# STB_PSU.net
KiCad netlist of a schematic drawn in Altium Designer
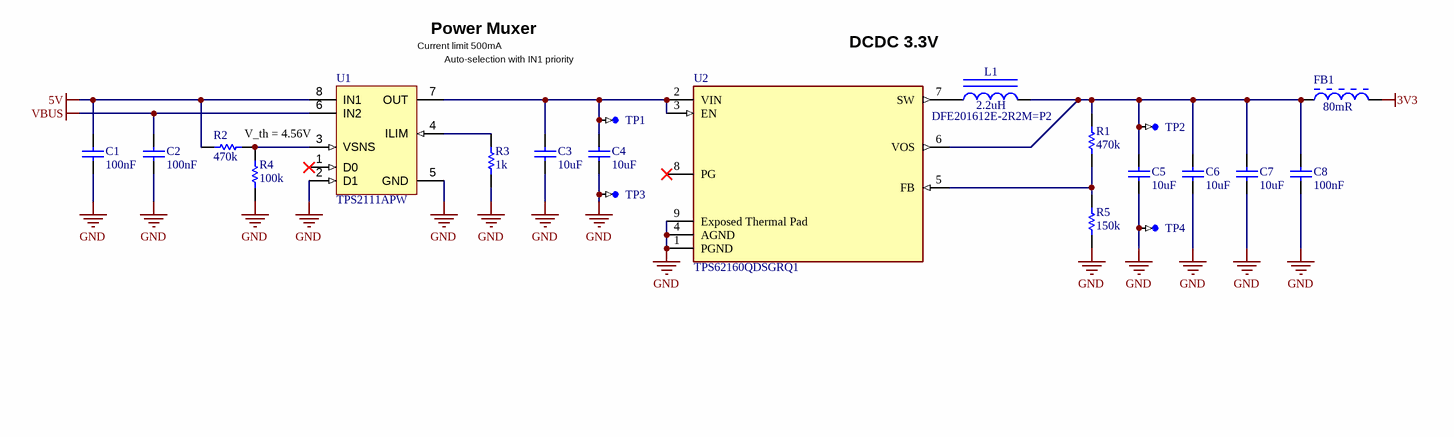
[diagram p0: STB_PSU.SchDoc]

(export (version "E")
  (design (tool "Eeschema 10.0.6"))
  (components
    (comp (ref "C1")
      (value "100nF")
      (footprint "CAPC1050X55X23LL05T13")
      (description "Chip Capacitor, 100 nF, +/- 10%, 16 V, -55 to 125 degC, 0402 (1005 Metric), RoHS, Tape and Reel")
      (fields
        (field (name "MANUFACTURER") "Samsung Electro-Mechanics")
        (field (name "MANUFACTURER PART NUMBER") "CL05B104KO5NNNC")
      )
      (libsource (lib "Altium Content Vault") (part "CAP-NP-2"))
    )
    (comp (ref "C2")
      (value "100nF")
      (footprint "CAPC1050X55X23LL05T13")
      (description "Chip Capacitor, 100 nF, +/- 10%, 16 V, -55 to 125 degC, 0402 (1005 Metric), RoHS, Tape and Reel")
      (fields
        (field (name "MANUFACTURER") "Samsung Electro-Mechanics")
        (field (name "MANUFACTURER PART NUMBER") "CL05B104KO5NNNC")
      )
      (libsource (lib "Altium Content Vault") (part "CAP-NP-2"))
    )
    (comp (ref "C3")
      (value "10uF")
      (footprint "CAPC0603(1608)100_L")
      (description "CAP 10uF 10V ±10% 0603 (1608 Metric) Thickness 1mm SMD")
      (fields (field (name "TOLERANCE") "Â±10%") (field (name "MANUFACTURER") "Samsung"))
      (libsource (lib "Altium Content Vault") (part "CMP-1035-02799-1"))
    )
    (comp (ref "C4")
      (value "10uF")
      (footprint "CAPC0603(1608)100_L")
      (description "CAP 10uF 10V ±10% 0603 (1608 Metric) Thickness 1mm SMD")
      (fields (field (name "TOLERANCE") "Â±10%") (field (name "MANUFACTURER") "Samsung"))
      (libsource (lib "Altium Content Vault") (part "CMP-1035-02799-1"))
    )
    (comp (ref "C5")
      (value "10uF")
      (footprint "CAPC0603(1608)100_L")
      (description "CAP 10uF 10V ±10% 0603 (1608 Metric) Thickness 1mm SMD")
      (fields (field (name "TOLERANCE") "Â±10%") (field (name "MANUFACTURER") "Samsung"))
      (libsource (lib "Altium Content Vault") (part "CMP-1035-02799-1"))
    )
    (comp (ref "C6")
      (value "10uF")
      (footprint "CAPC0603(1608)100_L")
      (description "CAP 10uF 10V ±10% 0603 (1608 Metric) Thickness 1mm SMD")
      (fields (field (name "TOLERANCE") "Â±10%") (field (name "MANUFACTURER") "Samsung"))
      (libsource (lib "Altium Content Vault") (part "CMP-1035-02799-1"))
    )
    (comp (ref "C7")
      (value "10uF")
      (footprint "CAPC0603(1608)100_L")
      (description "CAP 10uF 10V ±10% 0603 (1608 Metric) Thickness 1mm SMD")
      (fields (field (name "TOLERANCE") "Â±10%") (field (name "MANUFACTURER") "Samsung"))
      (libsource (lib "Altium Content Vault") (part "CMP-1035-02799-1"))
    )
    (comp (ref "C8")
      (value "100nF")
      (footprint "CAPC1050X55X23LL05T13")
      (description "Chip Capacitor, 100 nF, +/- 10%, 16 V, -55 to 125 degC, 0402 (1005 Metric), RoHS, Tape and Reel")
      (fields
        (field (name "MANUFACTURER") "Samsung Electro-Mechanics")
        (field (name "MANUFACTURER PART NUMBER") "CL05B104KO5NNNC")
      )
      (libsource (lib "Altium Content Vault") (part "CAP-NP-2"))
    )
    (comp (ref "FB1")
      (value "80mR")
      (footprint "MURA-BLM03-CHIP-2_V")
      (fields
        (field (name "MANUFACTURER") "Murata")
        (field (name "PARTNUMBER") "BLM03AX800SN1D")
        (field (name "TOLERANCE") "25%")
      )
      (libsource (lib "Altium Content Vault") (part "MURA-FB-2"))
    )
    (comp (ref "L1")
      (value "DFE201612E-2R2M=P2")
      (footprint "INDC2016X10L")
      (description "2.2µH Shielded Wirewound Inductor 1.8A 116mOhm Max 0806 (2016 Metric)")
      (fields
        (field (name "ALTIUM_VALUE") "2.2uH")
        (field (name "TOLERANCE") "±20%")
        (field (name "MANUFACTURER") "Murata Electronics")
      )
      (libsource (lib "ETHZ Vault") (part "Iron Core Inductor"))
    )
    (comp (ref "R1")
      (value "470k")
      (footprint "RESC1005X40X25LL05T10")
      (fields
        (field (name "PART NUMBER") "RC0402FR-07470KL")
        (field (name "MANUFACTURER") "Yageo / Phycomp")
        (field (name "TOLERANCE") "1%")
      )
      (libsource (lib "Altium Content Vault") (part "RES"))
    )
    (comp (ref "R2")
      (value "470k")
      (footprint "RESC1005X40X25LL05T10")
      (fields
        (field (name "PART NUMBER") "RC0402FR-07470KL")
        (field (name "MANUFACTURER") "Yageo / Phycomp")
        (field (name "TOLERANCE") "1%")
      )
      (libsource (lib "Altium Content Vault") (part "RES"))
    )
    (comp (ref "R3")
      (value "1k")
      (footprint "RESC1005X40X25LL05T10")
      (fields
        (field (name "PART NUMBER") "RC0402FR-071KL")
        (field (name "MANUFACTURER") "Yageo / Phycomp")
        (field (name "TOLERANCE") "1%")
      )
      (libsource (lib "Altium Content Vault") (part "RES"))
    )
    (comp (ref "R4")
      (value "100k")
      (footprint "RESC1005X40X25LL05T10")
      (fields
        (field (name "PART NUMBER") "RC0402FR-07100KL")
        (field (name "MANUFACTURER") "Yageo / Phycomp")
        (field (name "TOLERANCE") "1%")
      )
      (libsource (lib "Altium Content Vault") (part "RES"))
    )
    (comp (ref "R5")
      (value "150k")
      (footprint "RESC1005X40X25LL05T05")
      (fields
        (field (name "MANUFACTURER") "Yageo")
        (field (name "MANUFACTURER PART NUMBER") "RC0402FR-07150KL")
        (field (name "TOLERANCE") "1%")
      )
      (libsource (lib "Altium Content Vault") (part "RES"))
    )
    (comp (ref "TP1")
      (value "TP_1mm")
      (footprint "TP-SM-C-100")
      (description "testPoint 1mm")
      (libsource (lib "STB_Schlib") (part "testPoint_1mm"))
    )
    (comp (ref "TP2")
      (value "TP_1mm")
      (footprint "TP-SM-C-100")
      (description "testPoint 1mm")
      (libsource (lib "STB_Schlib") (part "testPoint_1mm"))
    )
    (comp (ref "TP3")
      (value "TP_1mm")
      (footprint "TP-SM-C-100")
      (description "testPoint 1mm")
      (libsource (lib "STB_Schlib") (part "testPoint_1mm"))
    )
    (comp (ref "TP4")
      (value "TP_1mm")
      (footprint "TP-SM-C-100")
      (description "testPoint 1mm")
      (libsource (lib "STB_Schlib") (part "testPoint_1mm"))
    )
    (comp (ref "U1")
      (value "TPS2111APW")
      (footprint "PW0008A_N")
      (fields (field (name "MANUFACTURER") "Texas Instruments"))
      (libsource (lib "Altium Content Vault") (part "TI-TPS2111APW8"))
    )
    (comp (ref "U2")
      (value "TPS62160QDSGRQ1")
      (footprint "FP-DSG0008A-IPC_C")
      (description "IC REG BUCK ADJUSTABLE 1A 8WSON")
      (fields (field (name "MANUFACTURER") "Texas Instruments"))
      (libsource (lib "Altium Content Vault") (part "e17a5803605875dd2ffdf80d518602c"))
    )
  )
  (nets
    (net (code "1") (name "3V3") (class "Default")
      (node (ref "FB1") (pin "2") (pinfunction "2_2") (pintype "passive"))
    )
    (net (code "2") (name "5V") (class "Default")
      (node (ref "C1") (pin "2") (pinfunction "2_2") (pintype "passive"))
      (node (ref "R2") (pin "2") (pinfunction "2_2") (pintype "passive"))
      (node (ref "U1") (pin "8") (pinfunction "IN1_8") (pintype "power_in"))
    )
    (net (code "3") (name "GND") (class "Default")
      (node (ref "C1") (pin "1") (pinfunction "1_1") (pintype "passive"))
      (node (ref "C2") (pin "1") (pinfunction "1_1") (pintype "passive"))
      (node (ref "C3") (pin "1") (pinfunction "1_1") (pintype "passive"))
      (node (ref "C4") (pin "1") (pinfunction "1_1") (pintype "passive"))
      (node (ref "C5") (pin "1") (pinfunction "1_1") (pintype "passive"))
      (node (ref "C6") (pin "1") (pinfunction "1_1") (pintype "passive"))
      (node (ref "C7") (pin "1") (pinfunction "1_1") (pintype "passive"))
      (node (ref "C8") (pin "1") (pinfunction "1_1") (pintype "passive"))
      (node (ref "R3") (pin "1") (pinfunction "1_1") (pintype "passive"))
      (node (ref "R4") (pin "2") (pinfunction "2_2") (pintype "passive"))
      (node (ref "R5") (pin "1") (pinfunction "1_1") (pintype "passive"))
      (node (ref "TP3") (pin "TP") (pinfunction "TP_TP") (pintype "input"))
      (node (ref "TP4") (pin "TP") (pinfunction "TP_TP") (pintype "input"))
      (node (ref "U1") (pin "2") (pinfunction "D1_2") (pintype "input"))
      (node (ref "U1") (pin "5") (pinfunction "GND_5") (pintype "power_in"))
      (node (ref "U2") (pin "1") (pinfunction "PGND_1") (pintype "power_in"))
      (node (ref "U2") (pin "4") (pinfunction "AGND_4") (pintype "power_in"))
      (node (ref "U2") (pin "9") (pinfunction "Exposed_Thermal_Pad_9") (pintype "power_in"))
    )
    (net (code "4") (name "Net-(U1-ILIM)") (class "Default")
      (node (ref "R3") (pin "2") (pinfunction "2_2") (pintype "passive"))
      (node (ref "U1") (pin "4") (pinfunction "ILIM_4") (pintype "input"))
    )
    (net (code "5") (name "Net-(U1-OUT)") (class "Default")
      (node (ref "C3") (pin "2") (pinfunction "2_2") (pintype "passive"))
      (node (ref "C4") (pin "2") (pinfunction "2_2") (pintype "passive"))
      (node (ref "TP1") (pin "TP") (pinfunction "TP_TP") (pintype "input"))
      (node (ref "U1") (pin "7") (pinfunction "OUT_7") (pintype "power_in"))
      (node (ref "U2") (pin "2") (pinfunction "VIN_2") (pintype "power_in"))
      (node (ref "U2") (pin "3") (pinfunction "EN_3") (pintype "input"))
    )
    (net (code "6") (name "Net-(U1-VSNS)") (class "Default")
      (node (ref "R2") (pin "1") (pinfunction "1_1") (pintype "passive"))
      (node (ref "R4") (pin "1") (pinfunction "1_1") (pintype "passive"))
      (node (ref "U1") (pin "3") (pinfunction "VSNS_3") (pintype "input"))
    )
    (net (code "7") (name "Net-(U2-FB)") (class "Default")
      (node (ref "R1") (pin "2") (pinfunction "2_2") (pintype "passive"))
      (node (ref "R5") (pin "2") (pinfunction "2_2") (pintype "passive"))
      (node (ref "U2") (pin "5") (pinfunction "FB_5") (pintype "input"))
    )
    (net (code "8") (name "Net-(U2-SW)") (class "Default")
      (node (ref "L1") (pin "1") (pinfunction "1_1") (pintype "passive"))
      (node (ref "U2") (pin "7") (pinfunction "SW_7") (pintype "output"))
    )
    (net (code "9") (name "Net-(U2-VOS)") (class "Default")
      (node (ref "C5") (pin "2") (pinfunction "2_2") (pintype "passive"))
      (node (ref "C6") (pin "2") (pinfunction "2_2") (pintype "passive"))
      (node (ref "C7") (pin "2") (pinfunction "2_2") (pintype "passive"))
      (node (ref "C8") (pin "2") (pinfunction "2_2") (pintype "passive"))
      (node (ref "FB1") (pin "1") (pinfunction "1_1") (pintype "passive"))
      (node (ref "L1") (pin "2") (pinfunction "2_2") (pintype "passive"))
      (node (ref "R1") (pin "1") (pinfunction "1_1") (pintype "passive"))
      (node (ref "TP2") (pin "TP") (pinfunction "TP_TP") (pintype "input"))
      (node (ref "U2") (pin "6") (pinfunction "VOS_6") (pintype "output"))
    )
    (net (code "10") (name "VBUS") (class "Default")
      (node (ref "C2") (pin "2") (pinfunction "2_2") (pintype "passive"))
      (node (ref "U1") (pin "6") (pinfunction "IN2_6") (pintype "power_in"))
    )
    (net (code "11") (name "unconnected-(U1-D0-Pad1)") (class "Default")
      (node (ref "U1") (pin "1") (pinfunction "D0_1") (pintype "input+no_connect"))
    )
    (net (code "12") (name "unconnected-(U2-PG-Pad8)") (class "Default")
      (node (ref "U2") (pin "8") (pinfunction "PG_8") (pintype "power_in+no_connect"))
    )
  )
)
